# CBB-EEProto-r1.net
KiCad netlist of a schematic drawn in EAGLE
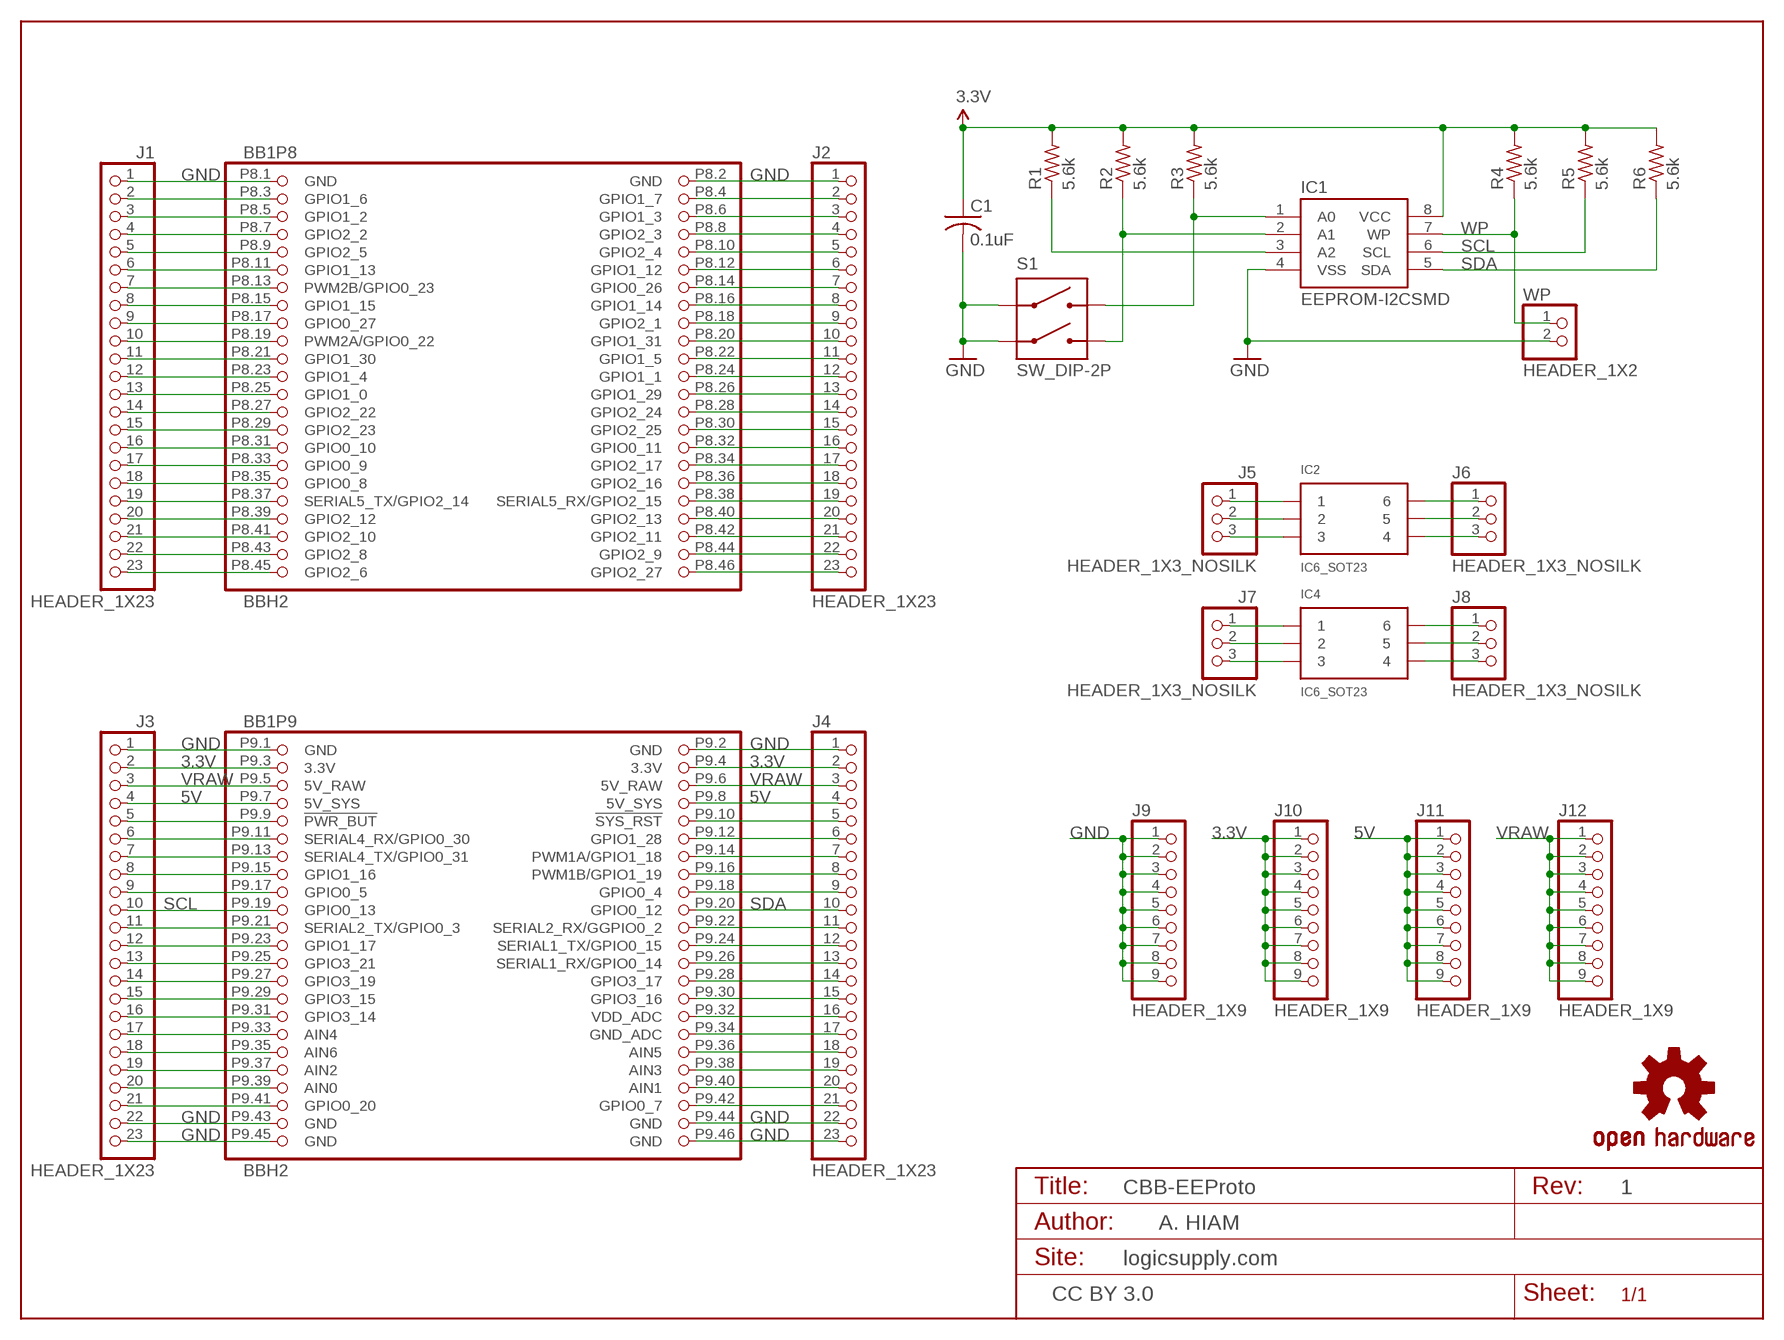
[diagram p0: schematic, sheet 1]

(export (version "E")
  (design (tool "Eeschema 10.0.6"))
  (components
    (comp (ref "BB1")
      (value "BBH2")
      (footprint "eagle-import:BB_CAPE_TOP")
      (libsource (lib "eagle-import") (part "BBH2"))
    )
    (comp (ref "C1")
      (value "0.1uF")
      (footprint "eagle-import:C0603")
      (libsource (lib "eagle-import") (part "C0603"))
    )
    (comp (ref "IC1")
      (value "EEPROM-I2CSMD")
      (footprint "eagle-import:SO08")
      (libsource (lib "eagle-import") (part "EEPROM-I2CSMD"))
    )
    (comp (ref "IC2")
      (value "IC6_SOT23")
      (footprint "eagle-import:SOT23-6")
      (libsource (lib "eagle-import") (part "IC6_SOT23"))
    )
    (comp (ref "IC4")
      (value "IC6_SOT23")
      (footprint "eagle-import:SOT23-6")
      (libsource (lib "eagle-import") (part "IC6_SOT23"))
    )
    (comp (ref "J1")
      (value "HEADER_1X23")
      (footprint "eagle-import:HEADER_1X23")
      (libsource (lib "eagle-import") (part "HEADER_1X23"))
    )
    (comp (ref "J2")
      (value "HEADER_1X23")
      (footprint "eagle-import:HEADER_1X23")
      (libsource (lib "eagle-import") (part "HEADER_1X23"))
    )
    (comp (ref "J3")
      (value "HEADER_1X23")
      (footprint "eagle-import:HEADER_1X23")
      (libsource (lib "eagle-import") (part "HEADER_1X23"))
    )
    (comp (ref "J4")
      (value "HEADER_1X23")
      (footprint "eagle-import:HEADER_1X23")
      (libsource (lib "eagle-import") (part "HEADER_1X23"))
    )
    (comp (ref "J5")
      (value "HEADER_1X3_NOSILK")
      (footprint "eagle-import:HEADER_1X3_NOSILK")
      (libsource (lib "eagle-import") (part "HEADER_1X3_NOSILK"))
    )
    (comp (ref "J6")
      (value "HEADER_1X3_NOSILK")
      (footprint "eagle-import:HEADER_1X3_NOSILK")
      (libsource (lib "eagle-import") (part "HEADER_1X3_NOSILK"))
    )
    (comp (ref "J7")
      (value "HEADER_1X3_NOSILK")
      (footprint "eagle-import:HEADER_1X3_NOSILK")
      (libsource (lib "eagle-import") (part "HEADER_1X3_NOSILK"))
    )
    (comp (ref "J8")
      (value "HEADER_1X3_NOSILK")
      (footprint "eagle-import:HEADER_1X3_NOSILK")
      (libsource (lib "eagle-import") (part "HEADER_1X3_NOSILK"))
    )
    (comp (ref "J9")
      (value "HEADER_1X9")
      (footprint "eagle-import:HEADER_1X9")
      (libsource (lib "eagle-import") (part "HEADER_1X9"))
    )
    (comp (ref "J10")
      (value "HEADER_1X9")
      (footprint "eagle-import:HEADER_1X9")
      (libsource (lib "eagle-import") (part "HEADER_1X9"))
    )
    (comp (ref "J11")
      (value "HEADER_1X9")
      (footprint "eagle-import:HEADER_1X9")
      (libsource (lib "eagle-import") (part "HEADER_1X9"))
    )
    (comp (ref "J12")
      (value "HEADER_1X9")
      (footprint "eagle-import:HEADER_1X9")
      (libsource (lib "eagle-import") (part "HEADER_1X9"))
    )
    (comp (ref "R1")
      (value "5.6k")
      (footprint "eagle-import:R0603")
      (libsource (lib "eagle-import") (part "R0603"))
    )
    (comp (ref "R2")
      (value "5.6k")
      (footprint "eagle-import:R0603")
      (libsource (lib "eagle-import") (part "R0603"))
    )
    (comp (ref "R3")
      (value "5.6k")
      (footprint "eagle-import:R0603")
      (libsource (lib "eagle-import") (part "R0603"))
    )
    (comp (ref "R4")
      (value "5.6k")
      (footprint "eagle-import:R0603")
      (libsource (lib "eagle-import") (part "R0603"))
    )
    (comp (ref "R5")
      (value "5.6k")
      (footprint "eagle-import:R0603")
      (libsource (lib "eagle-import") (part "R0603"))
    )
    (comp (ref "R6")
      (value "5.6k")
      (footprint "eagle-import:R0603")
      (libsource (lib "eagle-import") (part "R0603"))
    )
    (comp (ref "S1")
      (value "SW_DIP-2P")
      (footprint "eagle-import:DIPSWITCH-2P-SMD-1.27")
      (fields (field (name "PARTNO") "EHS102LD"))
      (libsource (lib "eagle-import") (part "SW_DIP-2P"))
    )
    (comp (ref "U$3")
      (value "OSHW-LOGOS")
      (footprint "eagle-import:OSHW-LOGO-S")
      (libsource (lib "eagle-import") (part "OSHW-LOGOS"))
    )
    (comp (ref "WP")
      (value "HEADER_1X2")
      (footprint "eagle-import:HEADER_1X2")
      (libsource (lib "eagle-import") (part "HEADER_1X2"))
    )
  )
  (nets
    (net (code "1") (name "/5V") (class "Default")
      (node (ref "BB1") (pin "P9.7") (pinfunction "5V_SYS_P9.7") (pintype "power_in"))
      (node (ref "BB1") (pin "P9.8") (pinfunction "5V_SYS_P9.8") (pintype "power_in"))
      (node (ref "J11") (pin "1") (pinfunction "1_1") (pintype "passive"))
      (node (ref "J11") (pin "2") (pinfunction "2_2") (pintype "passive"))
      (node (ref "J11") (pin "3") (pinfunction "3_3") (pintype "passive"))
      (node (ref "J11") (pin "4") (pinfunction "4_4") (pintype "passive"))
      (node (ref "J11") (pin "5") (pinfunction "5_5") (pintype "passive"))
      (node (ref "J11") (pin "6") (pinfunction "6_6") (pintype "passive"))
      (node (ref "J11") (pin "7") (pinfunction "7_7") (pintype "passive"))
      (node (ref "J11") (pin "8") (pinfunction "8_8") (pintype "passive"))
      (node (ref "J11") (pin "9") (pinfunction "9_9") (pintype "passive"))
      (node (ref "J3") (pin "4") (pinfunction "4_4") (pintype "passive"))
      (node (ref "J4") (pin "4") (pinfunction "4_4") (pintype "passive"))
    )
    (net (code "2") (name "/SCL") (class "Default")
      (node (ref "BB1") (pin "P9.19") (pinfunction "GPIO0_13_P9.19") (pintype "bidirectional"))
      (node (ref "IC1") (pin "6") (pinfunction "SCL_6") (pintype "bidirectional"))
      (node (ref "J3") (pin "10") (pinfunction "10_10") (pintype "passive"))
      (node (ref "R5") (pin "1") (pinfunction "1_1") (pintype "passive"))
    )
    (net (code "3") (name "/SDA") (class "Default")
      (node (ref "BB1") (pin "P9.20") (pinfunction "GPIO0_12_P9.20") (pintype "bidirectional"))
      (node (ref "IC1") (pin "5") (pinfunction "SDA_5") (pintype "bidirectional"))
      (node (ref "J4") (pin "10") (pinfunction "10_10") (pintype "passive"))
      (node (ref "R6") (pin "1") (pinfunction "1_1") (pintype "passive"))
    )
    (net (code "4") (name "/VRAW") (class "Default")
      (node (ref "BB1") (pin "P9.5") (pinfunction "5V_RAW_P9.5") (pintype "power_in"))
      (node (ref "BB1") (pin "P9.6") (pinfunction "5V_RAW_P9.6") (pintype "power_in"))
      (node (ref "J12") (pin "1") (pinfunction "1_1") (pintype "passive"))
      (node (ref "J12") (pin "2") (pinfunction "2_2") (pintype "passive"))
      (node (ref "J12") (pin "3") (pinfunction "3_3") (pintype "passive"))
      (node (ref "J12") (pin "4") (pinfunction "4_4") (pintype "passive"))
      (node (ref "J12") (pin "5") (pinfunction "5_5") (pintype "passive"))
      (node (ref "J12") (pin "6") (pinfunction "6_6") (pintype "passive"))
      (node (ref "J12") (pin "7") (pinfunction "7_7") (pintype "passive"))
      (node (ref "J12") (pin "8") (pinfunction "8_8") (pintype "passive"))
      (node (ref "J12") (pin "9") (pinfunction "9_9") (pintype "passive"))
      (node (ref "J3") (pin "3") (pinfunction "3_3") (pintype "passive"))
      (node (ref "J4") (pin "3") (pinfunction "3_3") (pintype "passive"))
    )
    (net (code "5") (name "/WP") (class "Default")
      (node (ref "IC1") (pin "7") (pinfunction "WP_7") (pintype "bidirectional"))
      (node (ref "R4") (pin "1") (pinfunction "1_1") (pintype "passive"))
      (node (ref "WP") (pin "1") (pinfunction "1_1") (pintype "passive"))
    )
    (net (code "6") (name "3.3V") (class "Default")
      (node (ref "BB1") (pin "P9.3") (pinfunction "3.3V_P9.3") (pintype "power_in"))
      (node (ref "BB1") (pin "P9.4") (pinfunction "3.3V_P9.4") (pintype "power_in"))
      (node (ref "C1") (pin "1") (pinfunction "1_1") (pintype "passive"))
      (node (ref "IC1") (pin "8") (pinfunction "VCC_8") (pintype "power_in"))
      (node (ref "J10") (pin "1") (pinfunction "1_1") (pintype "passive"))
      (node (ref "J10") (pin "2") (pinfunction "2_2") (pintype "passive"))
      (node (ref "J10") (pin "3") (pinfunction "3_3") (pintype "passive"))
      (node (ref "J10") (pin "4") (pinfunction "4_4") (pintype "passive"))
      (node (ref "J10") (pin "5") (pinfunction "5_5") (pintype "passive"))
      (node (ref "J10") (pin "6") (pinfunction "6_6") (pintype "passive"))
      (node (ref "J10") (pin "7") (pinfunction "7_7") (pintype "passive"))
      (node (ref "J10") (pin "8") (pinfunction "8_8") (pintype "passive"))
      (node (ref "J10") (pin "9") (pinfunction "9_9") (pintype "passive"))
      (node (ref "J3") (pin "2") (pinfunction "2_2") (pintype "passive"))
      (node (ref "J4") (pin "2") (pinfunction "2_2") (pintype "passive"))
      (node (ref "R1") (pin "2") (pinfunction "2_2") (pintype "passive"))
      (node (ref "R2") (pin "2") (pinfunction "2_2") (pintype "passive"))
      (node (ref "R3") (pin "2") (pinfunction "2_2") (pintype "passive"))
      (node (ref "R4") (pin "2") (pinfunction "2_2") (pintype "passive"))
      (node (ref "R5") (pin "2") (pinfunction "2_2") (pintype "passive"))
      (node (ref "R6") (pin "2") (pinfunction "2_2") (pintype "passive"))
    )
    (net (code "7") (name "GND") (class "Default")
      (node (ref "BB1") (pin "P8.1") (pinfunction "GND_P8.1") (pintype "power_in"))
      (node (ref "BB1") (pin "P8.2") (pinfunction "GND_P8.2") (pintype "power_in"))
      (node (ref "BB1") (pin "P9.1") (pinfunction "GND_P9.1") (pintype "power_in"))
      (node (ref "BB1") (pin "P9.2") (pinfunction "GND_P9.2") (pintype "power_in"))
      (node (ref "BB1") (pin "P9.43") (pinfunction "GND_P9.43") (pintype "bidirectional"))
      (node (ref "BB1") (pin "P9.44") (pinfunction "GND_P9.44") (pintype "bidirectional"))
      (node (ref "BB1") (pin "P9.45") (pinfunction "GND_P9.45") (pintype "bidirectional"))
      (node (ref "BB1") (pin "P9.46") (pinfunction "GND_P9.46") (pintype "bidirectional"))
      (node (ref "C1") (pin "2") (pinfunction "2_2") (pintype "passive"))
      (node (ref "IC1") (pin "4") (pinfunction "VSS_4") (pintype "power_in"))
      (node (ref "J1") (pin "1") (pinfunction "1_1") (pintype "passive"))
      (node (ref "J2") (pin "1") (pinfunction "1_1") (pintype "passive"))
      (node (ref "J3") (pin "1") (pinfunction "1_1") (pintype "passive"))
      (node (ref "J3") (pin "22") (pinfunction "22_22") (pintype "passive"))
      (node (ref "J3") (pin "23") (pinfunction "23_23") (pintype "passive"))
      (node (ref "J4") (pin "1") (pinfunction "1_1") (pintype "passive"))
      (node (ref "J4") (pin "22") (pinfunction "22_22") (pintype "passive"))
      (node (ref "J4") (pin "23") (pinfunction "23_23") (pintype "passive"))
      (node (ref "J9") (pin "1") (pinfunction "1_1") (pintype "passive"))
      (node (ref "J9") (pin "2") (pinfunction "2_2") (pintype "passive"))
      (node (ref "J9") (pin "3") (pinfunction "3_3") (pintype "passive"))
      (node (ref "J9") (pin "4") (pinfunction "4_4") (pintype "passive"))
      (node (ref "J9") (pin "5") (pinfunction "5_5") (pintype "passive"))
      (node (ref "J9") (pin "6") (pinfunction "6_6") (pintype "passive"))
      (node (ref "J9") (pin "7") (pinfunction "7_7") (pintype "passive"))
      (node (ref "J9") (pin "8") (pinfunction "8_8") (pintype "passive"))
      (node (ref "J9") (pin "9") (pinfunction "9_9") (pintype "passive"))
      (node (ref "S1") (pin "1A") (pinfunction "1A_1A") (pintype "bidirectional"))
      (node (ref "S1") (pin "2A") (pinfunction "2A_2A") (pintype "bidirectional"))
      (node (ref "WP") (pin "2") (pinfunction "2_2") (pintype "passive"))
    )
    (net (code "8") (name "Net-(BB1A-GPIO0_8)") (class "Default")
      (node (ref "BB1") (pin "P8.35") (pinfunction "GPIO0_8_P8.35") (pintype "bidirectional"))
      (node (ref "J1") (pin "18") (pinfunction "18_18") (pintype "passive"))
    )
    (net (code "9") (name "Net-(BB1A-GPIO0_9)") (class "Default")
      (node (ref "BB1") (pin "P8.33") (pinfunction "GPIO0_9_P8.33") (pintype "bidirectional"))
      (node (ref "J1") (pin "17") (pinfunction "17_17") (pintype "passive"))
    )
    (net (code "10") (name "Net-(BB1A-GPIO0_10)") (class "Default")
      (node (ref "BB1") (pin "P8.31") (pinfunction "GPIO0_10_P8.31") (pintype "bidirectional"))
      (node (ref "J1") (pin "16") (pinfunction "16_16") (pintype "passive"))
    )
    (net (code "11") (name "Net-(BB1A-GPIO0_11)") (class "Default")
      (node (ref "BB1") (pin "P8.32") (pinfunction "GPIO0_11_P8.32") (pintype "bidirectional"))
      (node (ref "J2") (pin "16") (pinfunction "16_16") (pintype "passive"))
    )
    (net (code "12") (name "Net-(BB1A-GPIO0_26)") (class "Default")
      (node (ref "BB1") (pin "P8.14") (pinfunction "GPIO0_26_P8.14") (pintype "bidirectional"))
      (node (ref "J2") (pin "7") (pinfunction "7_7") (pintype "passive"))
    )
    (net (code "13") (name "Net-(BB1A-GPIO0_27)") (class "Default")
      (node (ref "BB1") (pin "P8.17") (pinfunction "GPIO0_27_P8.17") (pintype "bidirectional"))
      (node (ref "J1") (pin "9") (pinfunction "9_9") (pintype "passive"))
    )
    (net (code "14") (name "Net-(BB1A-GPIO1_0)") (class "Default")
      (node (ref "BB1") (pin "P8.25") (pinfunction "GPIO1_0_P8.25") (pintype "bidirectional"))
      (node (ref "J1") (pin "13") (pinfunction "13_13") (pintype "passive"))
    )
    (net (code "15") (name "Net-(BB1A-GPIO1_1)") (class "Default")
      (node (ref "BB1") (pin "P8.24") (pinfunction "GPIO1_1_P8.24") (pintype "bidirectional"))
      (node (ref "J2") (pin "12") (pinfunction "12_12") (pintype "passive"))
    )
    (net (code "16") (name "Net-(BB1A-GPIO1_2)") (class "Default")
      (node (ref "BB1") (pin "P8.5") (pinfunction "GPIO1_2_P8.5") (pintype "bidirectional"))
      (node (ref "J1") (pin "3") (pinfunction "3_3") (pintype "passive"))
    )
    (net (code "17") (name "Net-(BB1A-GPIO1_3)") (class "Default")
      (node (ref "BB1") (pin "P8.6") (pinfunction "GPIO1_3_P8.6") (pintype "bidirectional"))
      (node (ref "J2") (pin "3") (pinfunction "3_3") (pintype "passive"))
    )
    (net (code "18") (name "Net-(BB1A-GPIO1_4)") (class "Default")
      (node (ref "BB1") (pin "P8.23") (pinfunction "GPIO1_4_P8.23") (pintype "bidirectional"))
      (node (ref "J1") (pin "12") (pinfunction "12_12") (pintype "passive"))
    )
    (net (code "19") (name "Net-(BB1A-GPIO1_5)") (class "Default")
      (node (ref "BB1") (pin "P8.22") (pinfunction "GPIO1_5_P8.22") (pintype "bidirectional"))
      (node (ref "J2") (pin "11") (pinfunction "11_11") (pintype "passive"))
    )
    (net (code "20") (name "Net-(BB1A-GPIO1_6)") (class "Default")
      (node (ref "BB1") (pin "P8.3") (pinfunction "GPIO1_6_P8.3") (pintype "bidirectional"))
      (node (ref "J1") (pin "2") (pinfunction "2_2") (pintype "passive"))
    )
    (net (code "21") (name "Net-(BB1A-GPIO1_7)") (class "Default")
      (node (ref "BB1") (pin "P8.4") (pinfunction "GPIO1_7_P8.4") (pintype "bidirectional"))
      (node (ref "J2") (pin "2") (pinfunction "2_2") (pintype "passive"))
    )
    (net (code "22") (name "Net-(BB1A-GPIO1_12)") (class "Default")
      (node (ref "BB1") (pin "P8.12") (pinfunction "GPIO1_12_P8.12") (pintype "bidirectional"))
      (node (ref "J2") (pin "6") (pinfunction "6_6") (pintype "passive"))
    )
    (net (code "23") (name "Net-(BB1A-GPIO1_13)") (class "Default")
      (node (ref "BB1") (pin "P8.11") (pinfunction "GPIO1_13_P8.11") (pintype "bidirectional"))
      (node (ref "J1") (pin "6") (pinfunction "6_6") (pintype "passive"))
    )
    (net (code "24") (name "Net-(BB1A-GPIO1_14)") (class "Default")
      (node (ref "BB1") (pin "P8.16") (pinfunction "GPIO1_14_P8.16") (pintype "bidirectional"))
      (node (ref "J2") (pin "8") (pinfunction "8_8") (pintype "passive"))
    )
    (net (code "25") (name "Net-(BB1A-GPIO1_15)") (class "Default")
      (node (ref "BB1") (pin "P8.15") (pinfunction "GPIO1_15_P8.15") (pintype "bidirectional"))
      (node (ref "J1") (pin "8") (pinfunction "8_8") (pintype "passive"))
    )
    (net (code "26") (name "Net-(BB1A-GPIO1_29)") (class "Default")
      (node (ref "BB1") (pin "P8.26") (pinfunction "GPIO1_29_P8.26") (pintype "bidirectional"))
      (node (ref "J2") (pin "13") (pinfunction "13_13") (pintype "passive"))
    )
    (net (code "27") (name "Net-(BB1A-GPIO1_30)") (class "Default")
      (node (ref "BB1") (pin "P8.21") (pinfunction "GPIO1_30_P8.21") (pintype "bidirectional"))
      (node (ref "J1") (pin "11") (pinfunction "11_11") (pintype "passive"))
    )
    (net (code "28") (name "Net-(BB1A-GPIO1_31)") (class "Default")
      (node (ref "BB1") (pin "P8.20") (pinfunction "GPIO1_31_P8.20") (pintype "bidirectional"))
      (node (ref "J2") (pin "10") (pinfunction "10_10") (pintype "passive"))
    )
    (net (code "29") (name "Net-(BB1A-GPIO2_1)") (class "Default")
      (node (ref "BB1") (pin "P8.18") (pinfunction "GPIO2_1_P8.18") (pintype "bidirectional"))
      (node (ref "J2") (pin "9") (pinfunction "9_9") (pintype "passive"))
    )
    (net (code "30") (name "Net-(BB1A-GPIO2_2)") (class "Default")
      (node (ref "BB1") (pin "P8.7") (pinfunction "GPIO2_2_P8.7") (pintype "bidirectional"))
      (node (ref "J1") (pin "4") (pinfunction "4_4") (pintype "passive"))
    )
    (net (code "31") (name "Net-(BB1A-GPIO2_3)") (class "Default")
      (node (ref "BB1") (pin "P8.8") (pinfunction "GPIO2_3_P8.8") (pintype "bidirectional"))
      (node (ref "J2") (pin "4") (pinfunction "4_4") (pintype "passive"))
    )
    (net (code "32") (name "Net-(BB1A-GPIO2_4)") (class "Default")
      (node (ref "BB1") (pin "P8.10") (pinfunction "GPIO2_4_P8.10") (pintype "bidirectional"))
      (node (ref "J2") (pin "5") (pinfunction "5_5") (pintype "passive"))
    )
    (net (code "33") (name "Net-(BB1A-GPIO2_5)") (class "Default")
      (node (ref "BB1") (pin "P8.9") (pinfunction "GPIO2_5_P8.9") (pintype "bidirectional"))
      (node (ref "J1") (pin "5") (pinfunction "5_5") (pintype "passive"))
    )
    (net (code "34") (name "Net-(BB1A-GPIO2_6)") (class "Default")
      (node (ref "BB1") (pin "P8.45") (pinfunction "GPIO2_6_P8.45") (pintype "bidirectional"))
      (node (ref "J1") (pin "23") (pinfunction "23_23") (pintype "passive"))
    )
    (net (code "35") (name "Net-(BB1A-GPIO2_8)") (class "Default")
      (node (ref "BB1") (pin "P8.43") (pinfunction "GPIO2_8_P8.43") (pintype "bidirectional"))
      (node (ref "J1") (pin "22") (pinfunction "22_22") (pintype "passive"))
    )
    (net (code "36") (name "Net-(BB1A-GPIO2_9)") (class "Default")
      (node (ref "BB1") (pin "P8.44") (pinfunction "GPIO2_9_P8.44") (pintype "bidirectional"))
      (node (ref "J2") (pin "22") (pinfunction "22_22") (pintype "passive"))
    )
    (net (code "37") (name "Net-(BB1A-GPIO2_10)") (class "Default")
      (node (ref "BB1") (pin "P8.41") (pinfunction "GPIO2_10_P8.41") (pintype "bidirectional"))
      (node (ref "J1") (pin "21") (pinfunction "21_21") (pintype "passive"))
    )
    (net (code "38") (name "Net-(BB1A-GPIO2_11)") (class "Default")
      (node (ref "BB1") (pin "P8.42") (pinfunction "GPIO2_11_P8.42") (pintype "bidirectional"))
      (node (ref "J2") (pin "21") (pinfunction "21_21") (pintype "passive"))
    )
    (net (code "39") (name "Net-(BB1A-GPIO2_12)") (class "Default")
      (node (ref "BB1") (pin "P8.39") (pinfunction "GPIO2_12_P8.39") (pintype "bidirectional"))
      (node (ref "J1") (pin "20") (pinfunction "20_20") (pintype "passive"))
    )
    (net (code "40") (name "Net-(BB1A-GPIO2_13)") (class "Default")
      (node (ref "BB1") (pin "P8.40") (pinfunction "GPIO2_13_P8.40") (pintype "bidirectional"))
      (node (ref "J2") (pin "20") (pinfunction "20_20") (pintype "passive"))
    )
    (net (code "41") (name "Net-(BB1A-GPIO2_16)") (class "Default")
      (node (ref "BB1") (pin "P8.36") (pinfunction "GPIO2_16_P8.36") (pintype "bidirectional"))
      (node (ref "J2") (pin "18") (pinfunction "18_18") (pintype "passive"))
    )
    (net (code "42") (name "Net-(BB1A-GPIO2_17)") (class "Default")
      (node (ref "BB1") (pin "P8.34") (pinfunction "GPIO2_17_P8.34") (pintype "bidirectional"))
      (node (ref "J2") (pin "17") (pinfunction "17_17") (pintype "passive"))
    )
    (net (code "43") (name "Net-(BB1A-GPIO2_22)") (class "Default")
      (node (ref "BB1") (pin "P8.27") (pinfunction "GPIO2_22_P8.27") (pintype "bidirectional"))
      (node (ref "J1") (pin "14") (pinfunction "14_14") (pintype "passive"))
    )
    (net (code "44") (name "Net-(BB1A-GPIO2_23)") (class "Default")
      (node (ref "BB1") (pin "P8.29") (pinfunction "GPIO2_23_P8.29") (pintype "bidirectional"))
      (node (ref "J1") (pin "15") (pinfunction "15_15") (pintype "passive"))
    )
    (net (code "45") (name "Net-(BB1A-GPIO2_24)") (class "Default")
      (node (ref "BB1") (pin "P8.28") (pinfunction "GPIO2_24_P8.28") (pintype "bidirectional"))
      (node (ref "J2") (pin "14") (pinfunction "14_14") (pintype "passive"))
    )
    (net (code "46") (name "Net-(BB1A-GPIO2_25)") (class "Default")
      (node (ref "BB1") (pin "P8.30") (pinfunction "GPIO2_25_P8.30") (pintype "bidirectional"))
      (node (ref "J2") (pin "15") (pinfunction "15_15") (pintype "passive"))
    )
    (net (code "47") (name "Net-(BB1A-GPIO2_27)") (class "Default")
      (node (ref "BB1") (pin "P8.46") (pinfunction "GPIO2_27_P8.46") (pintype "bidirectional"))
      (node (ref "J2") (pin "23") (pinfunction "23_23") (pintype "passive"))
    )
    (net (code "48") (name "Net-(BB1A-PWM2A{slash}GPIO0_22)") (class "Default")
      (node (ref "BB1") (pin "P8.19") (pinfunction "PWM2A/GPIO0_22_P8.19") (pintype "bidirectional"))
      (node (ref "J1") (pin "10") (pinfunction "10_10") (pintype "passive"))
    )
    (net (code "49") (name "Net-(BB1A-PWM2B{slash}GPIO0_23)") (class "Default")
      (node (ref "BB1") (pin "P8.13") (pinfunction "PWM2B/GPIO0_23_P8.13") (pintype "bidirectional"))
      (node (ref "J1") (pin "7") (pinfunction "7_7") (pintype "passive"))
    )
    (net (code "50") (name "Net-(BB1A-SERIAL5_RX{slash}GPIO2_15)") (class "Default")
      (node (ref "BB1") (pin "P8.38") (pinfunction "SERIAL5_RX/GPIO2_15_P8.38") (pintype "bidirectional"))
      (node (ref "J2") (pin "19") (pinfunction "19_19") (pintype "passive"))
    )
    (net (code "51") (name "Net-(BB1A-SERIAL5_TX{slash}GPIO2_14)") (class "Default")
      (node (ref "BB1") (pin "P8.37") (pinfunction "SERIAL5_TX/GPIO2_14_P8.37") (pintype "bidirectional"))
      (node (ref "J1") (pin "19") (pinfunction "19_19") (pintype "passive"))
    )
    (net (code "52") (name "Net-(BB1B-AIN0)") (class "Default")
      (node (ref "BB1") (pin "P9.39") (pinfunction "AIN0_P9.39") (pintype "input"))
      (node (ref "J3") (pin "20") (pinfunction "20_20") (pintype "passive"))
    )
    (net (code "53") (name "Net-(BB1B-AIN1)") (class "Default")
      (node (ref "BB1") (pin "P9.40") (pinfunction "AIN1_P9.40") (pintype "input"))
      (node (ref "J4") (pin "20") (pinfunction "20_20") (pintype "passive"))
    )
    (net (code "54") (name "Net-(BB1B-AIN2)") (class "Default")
      (node (ref "BB1") (pin "P9.37") (pinfunction "AIN2_P9.37") (pintype "input"))
      (node (ref "J3") (pin "19") (pinfunction "19_19") (pintype "passive"))
    )
    (net (code "55") (name "Net-(BB1B-AIN3)") (class "Default")
      (node (ref "BB1") (pin "P9.38") (pinfunction "AIN3_P9.38") (pintype "input"))
      (node (ref "J4") (pin "19") (pinfunction "19_19") (pintype "passive"))
    )
    (net (code "56") (name "Net-(BB1B-AIN4)") (class "Default")
      (node (ref "BB1") (pin "P9.33") (pinfunction "AIN4_P9.33") (pintype "input"))
      (node (ref "J3") (pin "17") (pinfunction "17_17") (pintype "passive"))
    )
    (net (code "57") (name "Net-(BB1B-AIN5)") (class "Default")
      (node (ref "BB1") (pin "P9.36") (pinfunction "AIN5_P9.36") (pintype "input"))
      (node (ref "J4") (pin "18") (pinfunction "18_18") (pintype "passive"))
    )
    (net (code "58") (name "Net-(BB1B-AIN6)") (class "Default")
      (node (ref "BB1") (pin "P9.35") (pinfunction "AIN6_P9.35") (pintype "input"))
      (node (ref "J3") (pin "18") (pinfunction "18_18") (pintype "passive"))
    )
    (net (code "59") (name "Net-(BB1B-GND_ADC)") (class "Default")
      (node (ref "BB1") (pin "P9.34") (pinfunction "GND_ADC_P9.34") (pintype "bidirectional"))
      (node (ref "J4") (pin "17") (pinfunction "17_17") (pintype "passive"))
    )
    (net (code "60") (name "Net-(BB1B-GPIO0_4)") (class "Default")
      (node (ref "BB1") (pin "P9.18") (pinfunction "GPIO0_4_P9.18") (pintype "bidirectional"))
      (node (ref "J4") (pin "9") (pinfunction "9_9") (pintype "passive"))
    )
    (net (code "61") (name "Net-(BB1B-GPIO0_5)") (class "Default")
      (node (ref "BB1") (pin "P9.17") (pinfunction "GPIO0_5_P9.17") (pintype "bidirectional"))
      (node (ref "J3") (pin "9") (pinfunction "9_9") (pintype "passive"))
    )
    (net (code "62") (name "Net-(BB1B-GPIO0_7)") (class "Default")
      (node (ref "BB1") (pin "P9.42") (pinfunction "GPIO0_7_P9.42") (pintype "bidirectional"))
      (node (ref "J4") (pin "21") (pinfunction "21_21") (pintype "passive"))
    )
    (net (code "63") (name "Net-(BB1B-GPIO0_20)") (class "Default")
      (node (ref "BB1") (pin "P9.41") (pinfunction "GPIO0_20_P9.41") (pintype "bidirectional"))
      (node (ref "J3") (pin "21") (pinfunction "21_21") (pintype "passive"))
    )
    (net (code "64") (name "Net-(BB1B-GPIO1_16)") (class "Default")
      (node (ref "BB1") (pin "P9.15") (pinfunction "GPIO1_16_P9.15") (pintype "bidirectional"))
      (node (ref "J3") (pin "8") (pinfunction "8_8") (pintype "passive"))
    )
    (net (code "65") (name "Net-(BB1B-GPIO1_17)") (class "Default")
      (node (ref "BB1") (pin "P9.23") (pinfunction "GPIO1_17_P9.23") (pintype "bidirectional"))
      (node (ref "J3") (pin "12") (pinfunction "12_12") (pintype "passive"))
    )
    (net (code "66") (name "Net-(BB1B-GPIO1_28)") (class "Default")
      (node (ref "BB1") (pin "P9.12") (pinfunction "GPIO1_28_P9.12") (pintype "bidirectional"))
      (node (ref "J4") (pin "6") (pinfunction "6_6") (pintype "passive"))
    )
    (net (code "67") (name "Net-(BB1B-GPIO3_14)") (class "Default")
      (node (ref "BB1") (pin "P9.31") (pinfunction "GPIO3_14_P9.31") (pintype "bidirectional"))
      (node (ref "J3") (pin "16") (pinfunction "16_16") (pintype "passive"))
    )
    (net (code "68") (name "Net-(BB1B-GPIO3_15)") (class "Default")
      (node (ref "BB1") (pin "P9.29") (pinfunction "GPIO3_15_P9.29") (pintype "bidirectional"))
      (node (ref "J3") (pin "15") (pinfunction "15_15") (pintype "passive"))
    )
    (net (code "69") (name "Net-(BB1B-GPIO3_16)") (class "Default")
      (node (ref "BB1") (pin "P9.30") (pinfunction "GPIO3_16_P9.30") (pintype "bidirectional"))
      (node (ref "J4") (pin "15") (pinfunction "15_15") (pintype "passive"))
    )
    (net (code "70") (name "Net-(BB1B-GPIO3_17)") (class "Default")
      (node (ref "BB1") (pin "P9.28") (pinfunction "GPIO3_17_P9.28") (pintype "bidirectional"))
      (node (ref "J4") (pin "14") (pinfunction "14_14") (pintype "passive"))
    )
    (net (code "71") (name "Net-(BB1B-GPIO3_19)") (class "Default")
      (node (ref "BB1") (pin "P9.27") (pinfunction "GPIO3_19_P9.27") (pintype "bidirectional"))
      (node (ref "J3") (pin "14") (pinfunction "14_14") (pintype "passive"))
    )
    (net (code "72") (name "Net-(BB1B-GPIO3_21)") (class "Default")
      (node (ref "BB1") (pin "P9.25") (pinfunction "GPIO3_21_P9.25") (pintype "bidirectional"))
      (node (ref "J3") (pin "13") (pinfunction "13_13") (pintype "passive"))
    )
    (net (code "73") (name "Net-(BB1B-PWM1A{slash}GPIO1_18)") (class "Default")
      (node (ref "BB1") (pin "P9.14") (pinfunction "PWM1A/GPIO1_18_P9.14") (pintype "bidirectional"))
      (node (ref "J4") (pin "7") (pinfunction "7_7") (pintype "passive"))
    )
    (net (code "74") (name "Net-(BB1B-PWM1B{slash}GPIO1_19)") (class "Default")
      (node (ref "BB1") (pin "P9.16") (pinfunction "PWM1B/GPIO1_19_P9.16") (pintype "bidirectional"))
      (node (ref "J4") (pin "8") (pinfunction "8_8") (pintype "passive"))
    )
    (net (code "75") (name "Net-(BB1B-SERIAL1_RX{slash}GPIO0_14)") (class "Default")
      (node (ref "BB1") (pin "P9.26") (pinfunction "SERIAL1_RX/GPIO0_14_P9.26") (pintype "bidirectional"))
      (node (ref "J4") (pin "13") (pinfunction "13_13") (pintype "passive"))
    )
    (net (code "76") (name "Net-(BB1B-SERIAL1_TX{slash}GPIO0_15)") (class "Default")
      (node (ref "BB1") (pin "P9.24") (pinfunction "SERIAL1_TX/GPIO0_15_P9.24") (pintype "bidirectional"))
      (node (ref "J4") (pin "12") (pinfunction "12_12") (pintype "passive"))
    )
    (net (code "77") (name "Net-(BB1B-SERIAL2_RX{slash}GGPIO0_2)") (class "Default")
      (node (ref "BB1") (pin "P9.22") (pinfunction "SERIAL2_RX/GGPIO0_2_P9.22") (pintype "bidirectional"))
      (node (ref "J4") (pin "11") (pinfunction "11_11") (pintype "passive"))
    )
    (net (code "78") (name "Net-(BB1B-SERIAL2_TX{slash}GPIO0_3)") (class "Default")
      (node (ref "BB1") (pin "P9.21") (pinfunction "SERIAL2_TX/GPIO0_3_P9.21") (pintype "bidirectional"))
      (node (ref "J3") (pin "11") (pinfunction "11_11") (pintype "passive"))
    )
    (net (code "79") (name "Net-(BB1B-SERIAL4_RX{slash}GPIO0_30)") (class "Default")
      (node (ref "BB1") (pin "P9.11") (pinfunction "SERIAL4_RX/GPIO0_30_P9.11") (pintype "bidirectional"))
      (node (ref "J3") (pin "6") (pinfunction "6_6") (pintype "passive"))
    )
    (net (code "80") (name "Net-(BB1B-SERIAL4_TX{slash}GPIO0_31)") (class "Default")
      (node (ref "BB1") (pin "P9.13") (pinfunction "SERIAL4_TX/GPIO0_31_P9.13") (pintype "bidirectional"))
      (node (ref "J3") (pin "7") (pinfunction "7_7") (pintype "passive"))
    )
    (net (code "81") (name "Net-(BB1B-VDD_ADC)") (class "Default")
      (node (ref "BB1") (pin "P9.32") (pinfunction "VDD_ADC_P9.32") (pintype "bidirectional"))
      (node (ref "J4") (pin "16") (pinfunction "16_16") (pintype "passive"))
    )
    (net (code "82") (name "Net-(BB1B-~{PWR_BUT})") (class "Default")
      (node (ref "BB1") (pin "P9.9") (pinfunction "~{PWR_BUT}_P9.9") (pintype "input"))
      (node (ref "J3") (pin "5") (pinfunction "5_5") (pintype "passive"))
    )
    (net (code "83") (name "Net-(BB1B-~{SYS_RST})") (class "Default")
      (node (ref "BB1") (pin "P9.10") (pinfunction "~{SYS_RST}_P9.10") (pintype "input"))
      (node (ref "J4") (pin "5") (pinfunction "5_5") (pintype "passive"))
    )
    (net (code "84") (name "Net-(IC1-A0)") (class "Default")
      (node (ref "IC1") (pin "1") (pinfunction "A0_1") (pintype "bidirectional"))
      (node (ref "R3") (pin "1") (pinfunction "1_1") (pintype "passive"))
      (node (ref "S1") (pin "1B") (pinfunction "1B_1B") (pintype "bidirectional"))
    )
    (net (code "85") (name "Net-(IC1-A1)") (class "Default")
      (node (ref "IC1") (pin "2") (pinfunction "A1_2") (pintype "bidirectional"))
      (node (ref "R2") (pin "1") (pinfunction "1_1") (pintype "passive"))
      (node (ref "S1") (pin "2B") (pinfunction "2B_2B") (pintype "bidirectional"))
    )
    (net (code "86") (name "Net-(IC1-A2)") (class "Default")
      (node (ref "IC1") (pin "3") (pinfunction "A2_3") (pintype "bidirectional"))
      (node (ref "R1") (pin "1") (pinfunction "1_1") (pintype "passive"))
    )
    (net (code "87") (name "Net-(IC2-Pad1)") (class "Default")
      (node (ref "IC2") (pin "1") (pinfunction "1_1") (pintype "bidirectional"))
      (node (ref "J5") (pin "1") (pinfunction "1_1") (pintype "passive"))
    )
    (net (code "88") (name "Net-(IC2-Pad2)") (class "Default")
      (node (ref "IC2") (pin "2") (pinfunction "2_2") (pintype "bidirectional"))
      (node (ref "J5") (pin "2") (pinfunction "2_2") (pintype "passive"))
    )
    (net (code "89") (name "Net-(IC2-Pad3)") (class "Default")
      (node (ref "IC2") (pin "3") (pinfunction "3_3") (pintype "bidirectional"))
      (node (ref "J5") (pin "3") (pinfunction "3_3") (pintype "passive"))
    )
    (net (code "90") (name "Net-(IC2-Pad4)") (class "Default")
      (node (ref "IC2") (pin "4") (pinfunction "4_4") (pintype "bidirectional"))
      (node (ref "J6") (pin "3") (pinfunction "3_3") (pintype "passive"))
    )
    (net (code "91") (name "Net-(IC2-Pad5)") (class "Default")
      (node (ref "IC2") (pin "5") (pinfunction "5_5") (pintype "bidirectional"))
      (node (ref "J6") (pin "2") (pinfunction "2_2") (pintype "passive"))
    )
    (net (code "92") (name "Net-(IC2-Pad6)") (class "Default")
      (node (ref "IC2") (pin "6") (pinfunction "6_6") (pintype "bidirectional"))
      (node (ref "J6") (pin "1") (pinfunction "1_1") (pintype "passive"))
    )
    (net (code "93") (name "Net-(IC4-Pad1)") (class "Default")
      (node (ref "IC4") (pin "1") (pinfunction "1_1") (pintype "bidirectional"))
      (node (ref "J7") (pin "1") (pinfunction "1_1") (pintype "passive"))
    )
    (net (code "94") (name "Net-(IC4-Pad2)") (class "Default")
      (node (ref "IC4") (pin "2") (pinfunction "2_2") (pintype "bidirectional"))
      (node (ref "J7") (pin "2") (pinfunction "2_2") (pintype "passive"))
    )
    (net (code "95") (name "Net-(IC4-Pad3)") (class "Default")
      (node (ref "IC4") (pin "3") (pinfunction "3_3") (pintype "bidirectional"))
      (node (ref "J7") (pin "3") (pinfunction "3_3") (pintype "passive"))
    )
    (net (code "96") (name "Net-(IC4-Pad4)") (class "Default")
      (node (ref "IC4") (pin "4") (pinfunction "4_4") (pintype "bidirectional"))
      (node (ref "J8") (pin "3") (pinfunction "3_3") (pintype "passive"))
    )
    (net (code "97") (name "Net-(IC4-Pad5)") (class "Default")
      (node (ref "IC4") (pin "5") (pinfunction "5_5") (pintype "bidirectional"))
      (node (ref "J8") (pin "2") (pinfunction "2_2") (pintype "passive"))
    )
    (net (code "98") (name "Net-(IC4-Pad6)") (class "Default")
      (node (ref "IC4") (pin "6") (pinfunction "6_6") (pintype "bidirectional"))
      (node (ref "J8") (pin "1") (pinfunction "1_1") (pintype "passive"))
    )
  )
)
